# STM32RF_PowerUSBSchDoc.net
KiCad netlist of a schematic drawn in Altium Designer
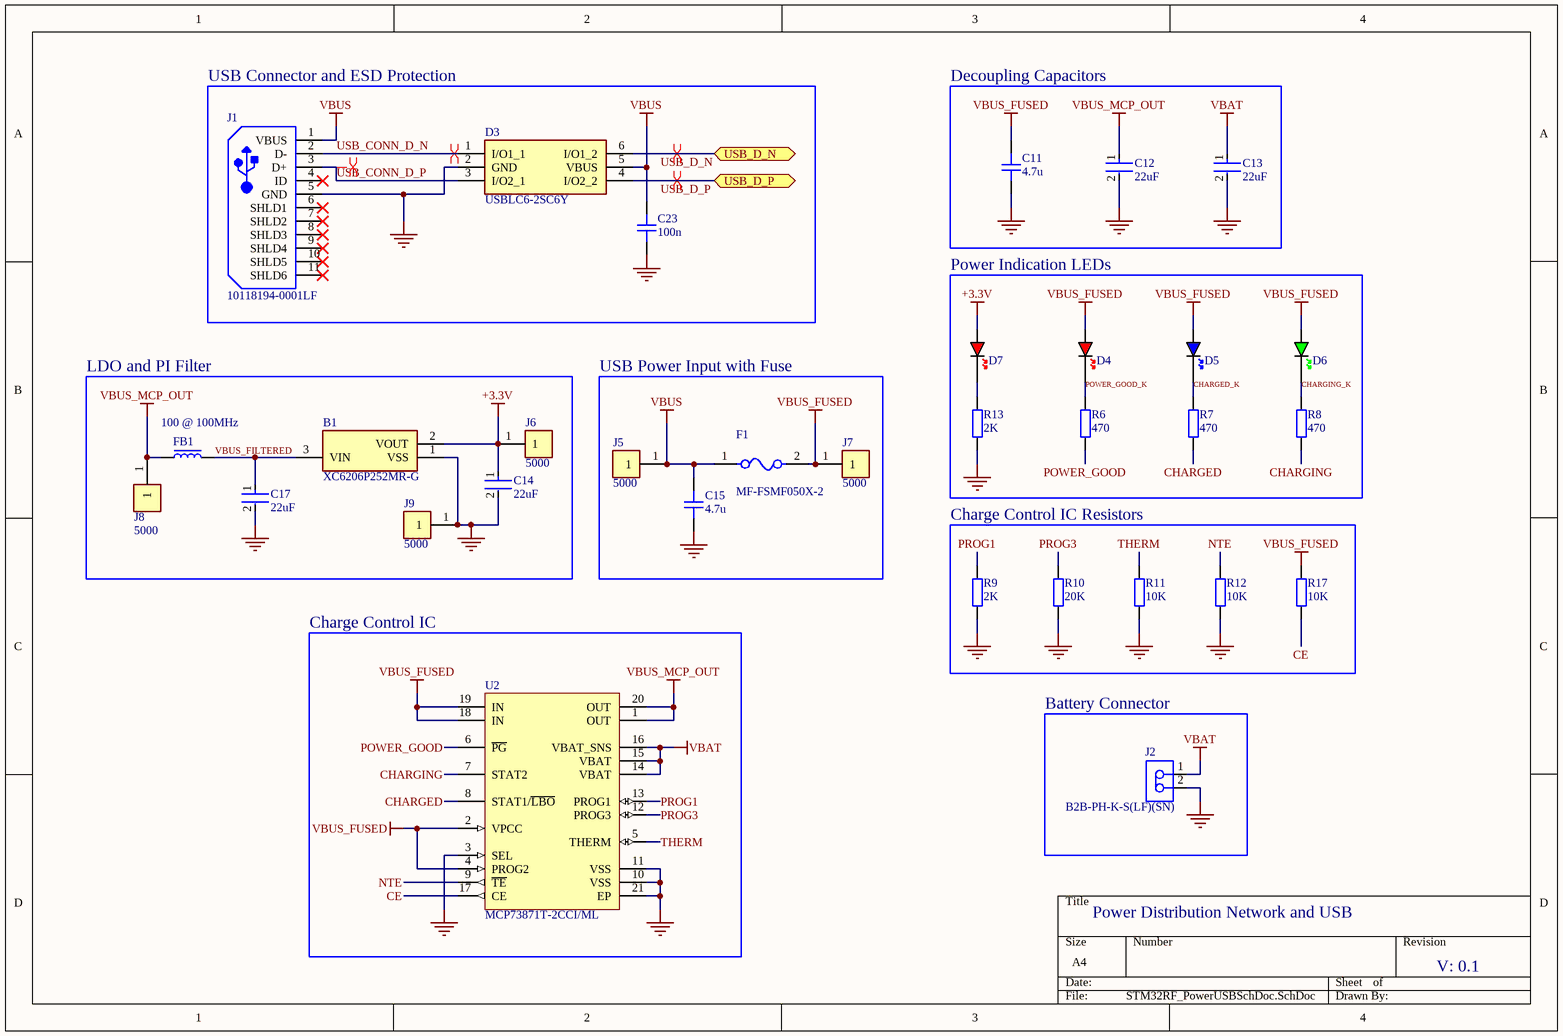
[diagram p0: STM32RF_PowerUSBSchDoc.SchDoc]

(export (version "E")
  (design (tool "Eeschema 10.0.6"))
  (components
    (comp (ref "B1")
      (value "XC6206P252MR-G")
      (footprint "SOT95P280X130-3N")
      (description "LDO Voltage Regulators 1uA Low Quiescent 3 Terminal, Low ESR Cap. Compatible, Voltage Regulator")
      (fields (field (name "MOUSER PART NUMBER") "865-XC6206P252MR-G"))
      (libsource (lib "XC6206P252MR-G") (part "XC6206P252MR-G"))
    )
    (comp (ref "C11")
      (value "4.7u")
      (footprint "CAP_0402")
      (description "Capacitor SMD 0402")
      (fields
        (field (name "MANUFACTURER") "Murata Electronics")
        (field (name "MANUFACTURER PART NUMBER") "GRM155R61E475ME15D")
      )
      (libsource (lib "Schematic-Lib-PhilsLab") (part "CAP_0402"))
    )
    (comp (ref "C12")
      (value "22uF")
      (footprint "FP-GRM158-0_2-MFG")
      (description "Chip Multilayer Ceramic Capacitors for General Purpose, 0402, 22uF, X5R, 15%, 20%, 10V")
      (libsource (lib "Altium Content Vault") (part "b4654b650e69147ec39a6b967a45e02"))
    )
    (comp (ref "C13")
      (value "22uF")
      (footprint "FP-GRM158-0_2-MFG")
      (description "Chip Multilayer Ceramic Capacitors for General Purpose, 0402, 22uF, X5R, 15%, 20%, 10V")
      (libsource (lib "Altium Content Vault") (part "b4654b650e69147ec39a6b967a45e02"))
    )
    (comp (ref "C14")
      (value "22uF")
      (footprint "FP-GRM158-0_2-MFG")
      (description "Chip Multilayer Ceramic Capacitors for General Purpose, 0402, 22uF, X5R, 15%, 20%, 10V")
      (libsource (lib "Altium Content Vault") (part "b4654b650e69147ec39a6b967a45e02"))
    )
    (comp (ref "C15")
      (value "4.7u")
      (footprint "CAP_0402")
      (description "Capacitor SMD 0402")
      (fields
        (field (name "MANUFACTURER") "Murata Electronics")
        (field (name "MANUFACTURER PART NUMBER") "GRM155R61E475ME15D")
      )
      (libsource (lib "Schematic-Lib-PhilsLab") (part "CAP_0402"))
    )
    (comp (ref "C17")
      (value "22uF")
      (footprint "FP-GRM158-0_2-MFG")
      (description "Chip Multilayer Ceramic Capacitors for General Purpose, 0402, 22uF, X5R, 15%, 20%, 10V")
      (libsource (lib "Altium Content Vault") (part "b4654b650e69147ec39a6b967a45e02"))
    )
    (comp (ref "C23")
      (value "100n")
      (footprint "CAP_0402")
      (description "Capacitor SMD 0402")
      (fields
        (field (name "MANUFACTURER") "Murata Electronics")
        (field (name "MANUFACTURER PART NUMBER") "GRM155R61E475ME15D")
      )
      (libsource (lib "Schematic-Lib-PhilsLab") (part "CAP_0402"))
    )
    (comp (ref "D3")
      (value "USBLC6-2SC6Y")
      (footprint "SOT95P280X145-6N")
      (fields (field (name "MOUSER PART NUMBER") "511-USBLC6-2SC6Y"))
      (libsource (lib "USBLC6-2SC6Y") (part "USBLC6-2SC6Y"))
    )
    (comp (ref "D4")
      (value "RED")
      (footprint "LED_0402_RED")
      (description "LED 0402 RED SMD")
      (libsource (lib "Schematic-Lib-PhilsLab") (part "LED_0402_RED"))
    )
    (comp (ref "D5")
      (value "BLUE")
      (footprint "LED_0402_BLUE")
      (description "LED 0402 BLUE SMD")
      (libsource (lib "Schematic-Lib-PhilsLab") (part "LED_0402_BLUE"))
    )
    (comp (ref "D6")
      (value "GREEN")
      (footprint "LED_0402_GREEN")
      (description "LED 0402 GREEN SMD")
      (libsource (lib "Schematic-Lib-PhilsLab") (part "LED_0402_GREEN"))
    )
    (comp (ref "D7")
      (value "RED")
      (footprint "LED_0402_RED")
      (description "LED 0402 RED SMD")
      (libsource (lib "Schematic-Lib-PhilsLab") (part "LED_0402_RED"))
    )
    (comp (ref "F1")
      (value "MF-FSMF050X-2")
      (footprint "FP-MF-FSMF-MFG")
      (description "PTC RESET FUSE 6V 500MA 0603")
      (fields
        (field (name "MANUFACTURER") "Bourns Inc.")
        (field (name "OCTOPART") "https://octopart.com/mf-fsmf050x-2-bourns-10470804")
      )
      (libsource (lib "Altium Content Vault") (part "5bcf9b9f640e542cf0359d10258e979"))
    )
    (comp (ref "FB1")
      (value "100 @ 100MHz")
      (footprint "FB_0603")
      (description "Ferrite Bead SMD 0603")
      (libsource (lib "Schematic-Lib-PhilsLab") (part "FB_0603"))
    )
    (comp (ref "J1")
      (value "10118194-0001LF")
      (footprint "FCI-10118194-0001LF-5_V")
      (description "Micro USB B Type Receptacle, 1.8 A, -55 to 85 degC, 5-Pin SMD, RoHS, Tape and Reel")
      (fields (field (name "MANUFACTURER") "Amphenol FCI"))
      (libsource (lib "Altium Content Vault") (part "USB-5-6SHLD"))
    )
    (comp (ref "J2")
      (value "B2B-PH-K-S(LF)(SN)")
      (footprint "JST-B2B-PH-K-S_V")
      (fields (field (name "MANUFACTURER") "JST"))
      (libsource (lib "Altium Content Vault") (part "CN-2P-F-QF2"))
    )
    (comp (ref "J5")
      (value "5000")
      (footprint "FP-5000-MFG")
      (description "PC TEST POINT MINIATURE RED")
      (libsource (lib "") (part "1e4615820a309e3ce90f9e6d957b7fa_1"))
    )
    (comp (ref "J6")
      (value "5000")
      (footprint "FP-5000-MFG")
      (description "PC TEST POINT MINIATURE RED")
      (libsource (lib "Altium Content Vault") (part "1e4615820a309e3ce90f9e6d957b7fa"))
    )
    (comp (ref "J7")
      (value "5000")
      (footprint "FP-5000-MFG")
      (description "PC TEST POINT MINIATURE RED")
      (libsource (lib "Altium Content Vault") (part "1e4615820a309e3ce90f9e6d957b7fa"))
    )
    (comp (ref "J8")
      (value "5000")
      (footprint "FP-5000-MFG")
      (description "PC TEST POINT MINIATURE RED")
      (libsource (lib "") (part "1e4615820a309e3ce90f9e6d957b7fa_2"))
    )
    (comp (ref "J9")
      (value "5000")
      (footprint "FP-5000-MFG")
      (description "PC TEST POINT MINIATURE RED")
      (libsource (lib "") (part "1e4615820a309e3ce90f9e6d957b7fa_1"))
    )
    (comp (ref "R6")
      (value "470")
      (footprint "RES_0402")
      (description "Resistor SMD 0402")
      (libsource (lib "Schematic-Lib-PhilsLab") (part "RES_0402"))
    )
    (comp (ref "R7")
      (value "470")
      (footprint "RES_0402")
      (description "Resistor SMD 0402")
      (libsource (lib "Schematic-Lib-PhilsLab") (part "RES_0402"))
    )
    (comp (ref "R8")
      (value "470")
      (footprint "RES_0402")
      (description "Resistor SMD 0402")
      (libsource (lib "Schematic-Lib-PhilsLab") (part "RES_0402"))
    )
    (comp (ref "R9")
      (value "2K")
      (footprint "RES_0402")
      (description "Resistor SMD 0402")
      (libsource (lib "Schematic-Lib-PhilsLab") (part "RES_0402"))
    )
    (comp (ref "R10")
      (value "20K")
      (footprint "RES_0402")
      (description "Resistor SMD 0402")
      (libsource (lib "Schematic-Lib-PhilsLab") (part "RES_0402"))
    )
    (comp (ref "R11")
      (value "10K")
      (footprint "RES_0402")
      (description "Resistor SMD 0402")
      (libsource (lib "Schematic-Lib-PhilsLab") (part "RES_0402"))
    )
    (comp (ref "R12")
      (value "10K")
      (footprint "RES_0402")
      (description "Resistor SMD 0402")
      (libsource (lib "Schematic-Lib-PhilsLab") (part "RES_0402"))
    )
    (comp (ref "R13")
      (value "2K")
      (footprint "RES_0402")
      (description "Resistor SMD 0402")
      (libsource (lib "Schematic-Lib-PhilsLab") (part "RES_0402"))
    )
    (comp (ref "R17")
      (value "10K")
      (footprint "RES_0402")
      (description "Resistor SMD 0402")
      (libsource (lib "Schematic-Lib-PhilsLab") (part "RES_0402"))
    )
    (comp (ref "U2")
      (value "MCP73871T-2CCI/ML")
      (footprint "QFN-ML20_L")
      (libsource (lib "Altium Content Vault") (part "PM-BM-MCP73871-SQ21"))
    )
  )
  (nets
    (net (code "1") (name "+3.3V") (class "Default")
      (node (ref "B1") (pin "2") (pinfunction "VOUT_2") (pintype "passive"))
      (node (ref "C14") (pin "1") (pinfunction "1_1") (pintype "passive"))
      (node (ref "D7") (pin "A") (pinfunction "A_A") (pintype "passive"))
      (node (ref "J6") (pin "1") (pinfunction "1_1") (pintype "passive"))
    )
    (net (code "2") (name "/CE") (class "Default")
      (node (ref "R17") (pin "1") (pinfunction "1_1") (pintype "passive"))
      (node (ref "U2") (pin "17") (pinfunction "CE_17") (pintype "output"))
    )
    (net (code "3") (name "/CHARGED") (class "Default")
      (node (ref "R7") (pin "1") (pinfunction "1_1") (pintype "passive"))
      (node (ref "U2") (pin "8") (pinfunction "STAT1/~{LBO}_8") (pintype "open_collector"))
    )
    (net (code "4") (name "/CHARGED_K") (class "Default")
      (node (ref "D5") (pin "K") (pinfunction "K_K") (pintype "passive"))
      (node (ref "R7") (pin "2") (pinfunction "2_2") (pintype "passive"))
    )
    (net (code "5") (name "/CHARGING") (class "Default")
      (node (ref "R8") (pin "1") (pinfunction "1_1") (pintype "passive"))
      (node (ref "U2") (pin "7") (pinfunction "STAT2_7") (pintype "open_collector"))
    )
    (net (code "6") (name "/CHARGING_K") (class "Default")
      (node (ref "D6") (pin "K") (pinfunction "K_K") (pintype "passive"))
      (node (ref "R8") (pin "2") (pinfunction "2_2") (pintype "passive"))
    )
    (net (code "7") (name "/NTE") (class "Default")
      (node (ref "R12") (pin "2") (pinfunction "2_2") (pintype "passive"))
      (node (ref "U2") (pin "9") (pinfunction "~{TE}_9") (pintype "output"))
    )
    (net (code "8") (name "/POWER_GOOD") (class "Default")
      (node (ref "R6") (pin "1") (pinfunction "1_1") (pintype "passive"))
      (node (ref "U2") (pin "6") (pinfunction "~{PG}_6") (pintype "open_collector"))
    )
    (net (code "9") (name "/POWER_GOOD_K") (class "Default")
      (node (ref "D4") (pin "K") (pinfunction "K_K") (pintype "passive"))
      (node (ref "R6") (pin "2") (pinfunction "2_2") (pintype "passive"))
    )
    (net (code "10") (name "/PROG1") (class "Default")
      (node (ref "R9") (pin "2") (pinfunction "2_2") (pintype "passive"))
      (node (ref "U2") (pin "13") (pinfunction "PROG1_13") (pintype "bidirectional"))
    )
    (net (code "11") (name "/PROG3") (class "Default")
      (node (ref "R10") (pin "2") (pinfunction "2_2") (pintype "passive"))
      (node (ref "U2") (pin "12") (pinfunction "PROG3_12") (pintype "bidirectional"))
    )
    (net (code "12") (name "/THERM") (class "Default")
      (node (ref "R11") (pin "2") (pinfunction "2_2") (pintype "passive"))
      (node (ref "U2") (pin "5") (pinfunction "THERM_5") (pintype "bidirectional"))
    )
    (net (code "13") (name "/USB_CONN_D_N") (class "Default")
      (node (ref "D3") (pin "1") (pinfunction "I/O1_1_1") (pintype "passive"))
      (node (ref "J1") (pin "2") (pinfunction "D-_2") (pintype "passive"))
    )
    (net (code "14") (name "/USB_CONN_D_P") (class "Default")
      (node (ref "D3") (pin "3") (pinfunction "I/O2_1_3") (pintype "passive"))
      (node (ref "J1") (pin "3") (pinfunction "D+_3") (pintype "passive"))
    )
    (net (code "15") (name "/USB_D_N") (class "Default")
      (node (ref "D3") (pin "6") (pinfunction "I/O1_2_6") (pintype "passive"))
    )
    (net (code "16") (name "/USB_D_P") (class "Default")
      (node (ref "D3") (pin "4") (pinfunction "I/O2_2_4") (pintype "passive"))
    )
    (net (code "17") (name "/VBUS_FILTERED") (class "Default")
      (node (ref "B1") (pin "3") (pinfunction "VIN_3") (pintype "passive"))
      (node (ref "C17") (pin "1") (pinfunction "1_1") (pintype "passive"))
      (node (ref "FB1") (pin "2") (pinfunction "2_2") (pintype "passive"))
    )
    (net (code "18") (name "GND") (class "Default")
      (node (ref "B1") (pin "1") (pinfunction "VSS_1") (pintype "passive"))
      (node (ref "C11") (pin "1") (pinfunction "1_1") (pintype "passive"))
      (node (ref "C12") (pin "2") (pinfunction "2_2") (pintype "passive"))
      (node (ref "C13") (pin "2") (pinfunction "2_2") (pintype "passive"))
      (node (ref "C14") (pin "2") (pinfunction "2_2") (pintype "passive"))
      (node (ref "C15") (pin "1") (pinfunction "1_1") (pintype "passive"))
      (node (ref "C17") (pin "2") (pinfunction "2_2") (pintype "passive"))
      (node (ref "C23") (pin "1") (pinfunction "1_1") (pintype "passive"))
      (node (ref "D3") (pin "2") (pinfunction "GND_2") (pintype "passive"))
      (node (ref "J1") (pin "5") (pinfunction "GND_5") (pintype "passive"))
      (node (ref "J2") (pin "2") (pinfunction "2_2") (pintype "passive"))
      (node (ref "J9") (pin "1") (pinfunction "1_1") (pintype "passive"))
      (node (ref "R10") (pin "1") (pinfunction "1_1") (pintype "passive"))
      (node (ref "R11") (pin "1") (pinfunction "1_1") (pintype "passive"))
      (node (ref "R12") (pin "1") (pinfunction "1_1") (pintype "passive"))
      (node (ref "R13") (pin "1") (pinfunction "1_1") (pintype "passive"))
      (node (ref "R9") (pin "1") (pinfunction "1_1") (pintype "passive"))
      (node (ref "U2") (pin "10") (pinfunction "VSS_10") (pintype "power_in"))
      (node (ref "U2") (pin "11") (pinfunction "VSS_11") (pintype "power_in"))
      (node (ref "U2") (pin "21") (pinfunction "EP_21") (pintype "power_in"))
      (node (ref "U2") (pin "3") (pinfunction "SEL_3") (pintype "input"))
    )
    (net (code "19") (name "Net-(D7-PadK)") (class "Default")
      (node (ref "D7") (pin "K") (pinfunction "K_K") (pintype "passive"))
      (node (ref "R13") (pin "2") (pinfunction "2_2") (pintype "passive"))
    )
    (net (code "20") (name "VBAT") (class "Default")
      (node (ref "C13") (pin "1") (pinfunction "1_1") (pintype "passive"))
      (node (ref "J2") (pin "1") (pinfunction "1_1") (pintype "passive"))
      (node (ref "U2") (pin "14") (pinfunction "VBAT_14") (pintype "power_in"))
      (node (ref "U2") (pin "15") (pinfunction "VBAT_15") (pintype "power_in"))
      (node (ref "U2") (pin "16") (pinfunction "VBAT_SNS_16") (pintype "power_in"))
    )
    (net (code "21") (name "VBUS") (class "Default")
      (node (ref "C15") (pin "2") (pinfunction "2_2") (pintype "passive"))
      (node (ref "C23") (pin "2") (pinfunction "2_2") (pintype "passive"))
      (node (ref "D3") (pin "5") (pinfunction "VBUS_5") (pintype "passive"))
      (node (ref "F1") (pin "1") (pinfunction "1_1") (pintype "passive"))
      (node (ref "J1") (pin "1") (pinfunction "VBUS_1") (pintype "passive"))
      (node (ref "J5") (pin "1") (pinfunction "1_1") (pintype "passive"))
    )
    (net (code "22") (name "VBUS_FUSED") (class "Default")
      (node (ref "C11") (pin "2") (pinfunction "2_2") (pintype "passive"))
      (node (ref "D4") (pin "A") (pinfunction "A_A") (pintype "passive"))
      (node (ref "D5") (pin "A") (pinfunction "A_A") (pintype "passive"))
      (node (ref "D6") (pin "A") (pinfunction "A_A") (pintype "passive"))
      (node (ref "F1") (pin "2") (pinfunction "2_2") (pintype "passive"))
      (node (ref "J7") (pin "1") (pinfunction "1_1") (pintype "passive"))
      (node (ref "R17") (pin "2") (pinfunction "2_2") (pintype "passive"))
      (node (ref "U2") (pin "18") (pinfunction "IN_18") (pintype "power_in"))
      (node (ref "U2") (pin "19") (pinfunction "IN_19") (pintype "power_in"))
      (node (ref "U2") (pin "2") (pinfunction "VPCC_2") (pintype "input"))
      (node (ref "U2") (pin "4") (pinfunction "PROG2_4") (pintype "input"))
    )
    (net (code "23") (name "VBUS_MCP_OUT") (class "Default")
      (node (ref "C12") (pin "1") (pinfunction "1_1") (pintype "passive"))
      (node (ref "FB1") (pin "1") (pinfunction "1_1") (pintype "passive"))
      (node (ref "J8") (pin "1") (pinfunction "1_1") (pintype "passive"))
      (node (ref "U2") (pin "1") (pinfunction "OUT_1") (pintype "power_in"))
      (node (ref "U2") (pin "20") (pinfunction "OUT_20") (pintype "power_in"))
    )
    (net (code "24") (name "unconnected-(J1-ID-Pad4)") (class "Default")
      (node (ref "J1") (pin "4") (pinfunction "ID_4") (pintype "passive+no_connect"))
    )
    (net (code "25") (name "unconnected-(J1-SHLD1-Pad6)") (class "Default")
      (node (ref "J1") (pin "6") (pinfunction "SHLD1_6") (pintype "passive+no_connect"))
    )
    (net (code "26") (name "unconnected-(J1-SHLD2-Pad7)") (class "Default")
      (node (ref "J1") (pin "7") (pinfunction "SHLD2_7") (pintype "passive+no_connect"))
    )
    (net (code "27") (name "unconnected-(J1-SHLD3-Pad8)") (class "Default")
      (node (ref "J1") (pin "8") (pinfunction "SHLD3_8") (pintype "passive+no_connect"))
    )
    (net (code "28") (name "unconnected-(J1-SHLD4-Pad9)") (class "Default")
      (node (ref "J1") (pin "9") (pinfunction "SHLD4_9") (pintype "passive+no_connect"))
    )
    (net (code "29") (name "unconnected-(J1-SHLD5-Pad10)") (class "Default")
      (node (ref "J1") (pin "10") (pinfunction "SHLD5_10") (pintype "passive+no_connect"))
    )
    (net (code "30") (name "unconnected-(J1-SHLD6-Pad11)") (class "Default")
      (node (ref "J1") (pin "11") (pinfunction "SHLD6_11") (pintype "passive+no_connect"))
    )
  )
)
